# PiPowerV1.net
KiCad netlist of a schematic drawn in EAGLE
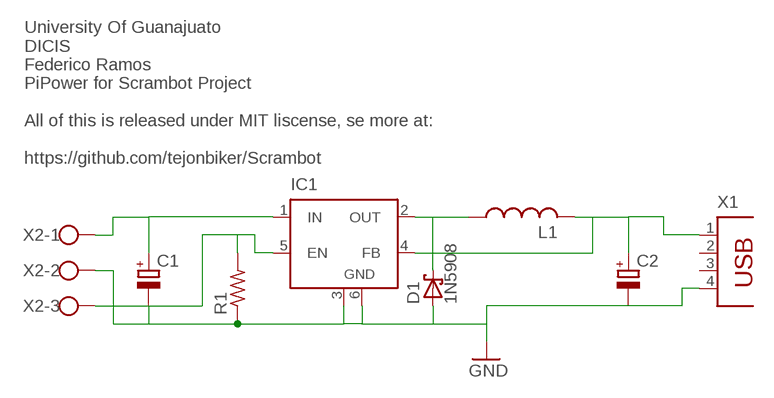
[diagram p0: schematic, sheet 1]

(export (version "E")
  (design (tool "Eeschema 10.0.6"))
  (components
    (comp (ref "C1")
      (value "CPOL-EUE3.5-10")
      (footprint "eagle-import:E3,5-10")
      (libsource (lib "eagle-import") (part "CPOL-EUE3.5-10"))
    )
    (comp (ref "C2")
      (value "CPOL-EUE3.5-10")
      (footprint "eagle-import:E3,5-10")
      (libsource (lib "eagle-import") (part "CPOL-EUE3.5-10"))
    )
    (comp (ref "D1")
      (value "1N5908")
      (footprint "eagle-import:C4111-15")
      (libsource (lib "eagle-import") (part "1N5908"))
    )
    (comp (ref "IC1")
      (value "LM2596S")
      (footprint "eagle-import:TO263-5")
      (libsource (lib "eagle-import") (part "LM2596S"))
    )
    (comp (ref "L1")
      (value "L-US0204/5")
      (footprint "eagle-import:0204_5")
      (libsource (lib "eagle-import") (part "L-US0204/5"))
    )
    (comp (ref "R1")
      (value "R-US_M1206")
      (footprint "eagle-import:M1206")
      (libsource (lib "eagle-import") (part "R-US_M1206"))
    )
    (comp (ref "X1")
      (value "PN87520")
      (footprint "eagle-import:PN87520")
      (libsource (lib "eagle-import") (part "PN87520"))
    )
    (comp (ref "X2")
      (value "W237-103")
      (footprint "eagle-import:W237-103")
      (fields (field (name "MPN") "237-103"))
      (libsource (lib "eagle-import") (part "W237-103"))
    )
  )
  (nets
    (net (code "1") (name "GND") (class "Default")
      (node (ref "C1") (pin "-") (pinfunction "-_-") (pintype "passive"))
      (node (ref "C2") (pin "-") (pinfunction "-_-") (pintype "passive"))
      (node (ref "D1") (pin "A") (pinfunction "A_A") (pintype "passive"))
      (node (ref "IC1") (pin "3") (pinfunction "GND_3") (pintype "power_in"))
      (node (ref "IC1") (pin "6") (pinfunction "GND_6") (pintype "power_in"))
      (node (ref "R1") (pin "1") (pinfunction "1_1") (pintype "passive"))
      (node (ref "X1") (pin "4") (pinfunction "4_4") (pintype "passive"))
      (node (ref "X2") (pin "2") (pinfunction "KL_2") (pintype "passive"))
    )
    (net (code "2") (name "Net-(IC1-EN)") (class "Default")
      (node (ref "IC1") (pin "5") (pinfunction "EN_5") (pintype "input"))
      (node (ref "R1") (pin "2") (pinfunction "2_2") (pintype "passive"))
      (node (ref "X2") (pin "3") (pinfunction "KL_3") (pintype "passive"))
    )
    (net (code "3") (name "Net-(IC1-FB)") (class "Default")
      (node (ref "C2") (pin "+") (pinfunction "+_+") (pintype "passive"))
      (node (ref "IC1") (pin "4") (pinfunction "FB_4") (pintype "input"))
      (node (ref "L1") (pin "2") (pinfunction "2_2") (pintype "passive"))
      (node (ref "X1") (pin "1") (pinfunction "1_1") (pintype "passive"))
    )
    (net (code "4") (name "Net-(IC1-IN)") (class "Default")
      (node (ref "C1") (pin "+") (pinfunction "+_+") (pintype "passive"))
      (node (ref "IC1") (pin "1") (pinfunction "IN_1") (pintype "input"))
      (node (ref "X2") (pin "1") (pinfunction "KL_1") (pintype "passive"))
    )
    (net (code "5") (name "Net-(IC1-OUT)") (class "Default")
      (node (ref "D1") (pin "C") (pinfunction "C_C") (pintype "passive"))
      (node (ref "IC1") (pin "2") (pinfunction "OUT_2") (pintype "output"))
      (node (ref "L1") (pin "1") (pinfunction "1_1") (pintype "passive"))
    )
    (net (code "6") (name "unconnected-(X1-Pad2)") (class "Default")
      (node (ref "X1") (pin "2") (pinfunction "2_2") (pintype "passive"))
    )
    (net (code "7") (name "unconnected-(X1-Pad3)") (class "Default")
      (node (ref "X1") (pin "3") (pinfunction "3_3") (pintype "passive"))
    )
  )
)
